# Mode_Switch.net
KiCad netlist of a schematic drawn in Altium Designer
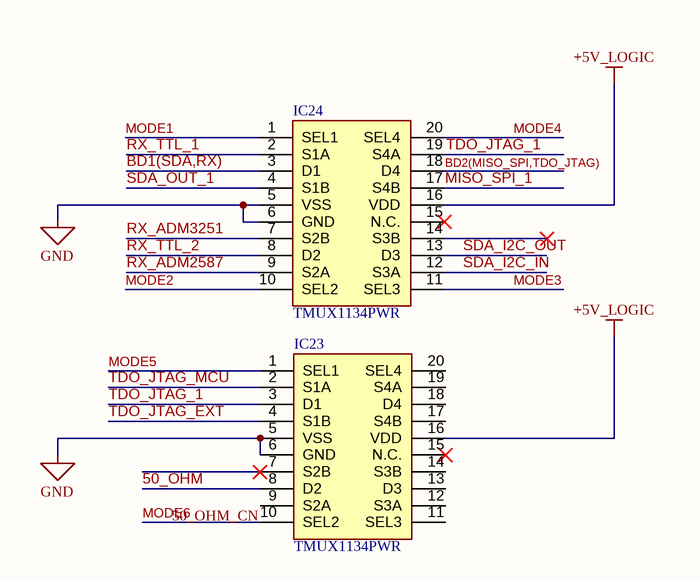
[diagram p0: Mode Switch.SchDoc]

(export (version "E")
  (design (tool "Eeschema 10.0.6"))
  (components
    (comp (ref "IC23")
      (value "TMUX1134PWR")
      (footprint "SamacSys:SOP65P640X120-20N")
      (description "Integrated Circuit")
      (fields (field (name "MOUSER PART NUMBER") "595-TMUX1134PWR"))
      (libsource (lib "*") (part "TMUX1134PWR"))
    )
    (comp (ref "IC24")
      (value "TMUX1134PWR")
      (footprint "SamacSys:SOP65P640X120-20N")
      (description "Integrated Circuit")
      (fields (field (name "MOUSER PART NUMBER") "595-TMUX1134PWR"))
      (libsource (lib "*") (part "TMUX1134PWR"))
    )
  )
  (nets
    (net (code "1") (name "+5V_LOGIC") (class "Default")
      (node (ref "IC23") (pin "16") (pinfunction "VDD_16") (pintype "passive"))
      (node (ref "IC24") (pin "16") (pinfunction "VDD_16") (pintype "passive"))
    )
    (net (code "2") (name "/50_OHM") (class "Default")
      (node (ref "IC23") (pin "8") (pinfunction "D2_8") (pintype "passive"))
    )
    (net (code "3") (name "/50_OHM_CN") (class "Default")
      (node (ref "IC23") (pin "9") (pinfunction "S2A_9") (pintype "passive"))
    )
    (net (code "4") (name "/BD1(SDA,RX)") (class "Default")
      (node (ref "IC24") (pin "3") (pinfunction "D1_3") (pintype "passive"))
    )
    (net (code "5") (name "/BD2(MISO_SPI,TDO_JTAG)") (class "Default")
      (node (ref "IC24") (pin "18") (pinfunction "D4_18") (pintype "passive"))
    )
    (net (code "6") (name "/MISO_SPI_1") (class "Default")
      (node (ref "IC24") (pin "17") (pinfunction "S4B_17") (pintype "passive"))
    )
    (net (code "7") (name "/MODE1") (class "Default")
      (node (ref "IC24") (pin "1") (pinfunction "SEL1_1") (pintype "passive"))
    )
    (net (code "8") (name "/MODE2") (class "Default")
      (node (ref "IC24") (pin "10") (pinfunction "SEL2_10") (pintype "passive"))
    )
    (net (code "9") (name "/MODE3") (class "Default")
      (node (ref "IC24") (pin "11") (pinfunction "SEL3_11") (pintype "passive"))
    )
    (net (code "10") (name "/MODE4") (class "Default")
      (node (ref "IC24") (pin "20") (pinfunction "SEL4_20") (pintype "passive"))
    )
    (net (code "11") (name "/MODE5") (class "Default")
      (node (ref "IC23") (pin "1") (pinfunction "SEL1_1") (pintype "passive"))
    )
    (net (code "12") (name "/MODE6") (class "Default")
      (node (ref "IC23") (pin "10") (pinfunction "SEL2_10") (pintype "passive"))
    )
    (net (code "13") (name "/RX_ADM2587") (class "Default")
      (node (ref "IC24") (pin "9") (pinfunction "S2A_9") (pintype "passive"))
    )
    (net (code "14") (name "/RX_ADM3251") (class "Default")
      (node (ref "IC24") (pin "7") (pinfunction "S2B_7") (pintype "passive"))
    )
    (net (code "15") (name "/RX_TTL_1") (class "Default")
      (node (ref "IC24") (pin "2") (pinfunction "S1A_2") (pintype "passive"))
    )
    (net (code "16") (name "/RX_TTL_2") (class "Default")
      (node (ref "IC24") (pin "8") (pinfunction "D2_8") (pintype "passive"))
    )
    (net (code "17") (name "/SDA_I2C_IN") (class "Default")
      (node (ref "IC24") (pin "12") (pinfunction "S3A_12") (pintype "passive"))
    )
    (net (code "18") (name "/SDA_I2C_OUT") (class "Default")
      (node (ref "IC24") (pin "13") (pinfunction "D3_13") (pintype "passive"))
    )
    (net (code "19") (name "/SDA_OUT_1") (class "Default")
      (node (ref "IC24") (pin "4") (pinfunction "S1B_4") (pintype "passive"))
    )
    (net (code "20") (name "/TDO_JTAG_1") (class "Default")
      (node (ref "IC23") (pin "3") (pinfunction "D1_3") (pintype "passive"))
      (node (ref "IC24") (pin "19") (pinfunction "S4A_19") (pintype "passive"))
    )
    (net (code "21") (name "/TDO_JTAG_EXT") (class "Default")
      (node (ref "IC23") (pin "4") (pinfunction "S1B_4") (pintype "passive"))
    )
    (net (code "22") (name "/TDO_JTAG_MCU") (class "Default")
      (node (ref "IC23") (pin "2") (pinfunction "S1A_2") (pintype "passive"))
    )
    (net (code "23") (name "GND") (class "Default")
      (node (ref "IC23") (pin "5") (pinfunction "VSS_5") (pintype "passive"))
      (node (ref "IC23") (pin "6") (pinfunction "GND_6") (pintype "passive"))
      (node (ref "IC24") (pin "5") (pinfunction "VSS_5") (pintype "passive"))
      (node (ref "IC24") (pin "6") (pinfunction "GND_6") (pintype "passive"))
    )
    (net (code "24") (name "unconnected-(IC23-D3-Pad13)") (class "Default")
      (node (ref "IC23") (pin "13") (pinfunction "D3_13") (pintype "passive"))
    )
    (net (code "25") (name "unconnected-(IC23-D4-Pad18)") (class "Default")
      (node (ref "IC23") (pin "18") (pinfunction "D4_18") (pintype "passive"))
    )
    (net (code "26") (name "unconnected-(IC23-N.C.-Pad15)") (class "Default")
      (node (ref "IC23") (pin "15") (pinfunction "N.C._15") (pintype "passive+no_connect"))
    )
    (net (code "27") (name "unconnected-(IC23-S2B-Pad7)") (class "Default")
      (node (ref "IC23") (pin "7") (pinfunction "S2B_7") (pintype "passive+no_connect"))
    )
    (net (code "28") (name "unconnected-(IC23-S3A-Pad12)") (class "Default")
      (node (ref "IC23") (pin "12") (pinfunction "S3A_12") (pintype "passive"))
    )
    (net (code "29") (name "unconnected-(IC23-S3B-Pad14)") (class "Default")
      (node (ref "IC23") (pin "14") (pinfunction "S3B_14") (pintype "passive"))
    )
    (net (code "30") (name "unconnected-(IC23-S4A-Pad19)") (class "Default")
      (node (ref "IC23") (pin "19") (pinfunction "S4A_19") (pintype "passive"))
    )
    (net (code "31") (name "unconnected-(IC23-S4B-Pad17)") (class "Default")
      (node (ref "IC23") (pin "17") (pinfunction "S4B_17") (pintype "passive"))
    )
    (net (code "32") (name "unconnected-(IC23-SEL3-Pad11)") (class "Default")
      (node (ref "IC23") (pin "11") (pinfunction "SEL3_11") (pintype "passive"))
    )
    (net (code "33") (name "unconnected-(IC23-SEL4-Pad20)") (class "Default")
      (node (ref "IC23") (pin "20") (pinfunction "SEL4_20") (pintype "passive"))
    )
    (net (code "34") (name "unconnected-(IC24-N.C.-Pad15)") (class "Default")
      (node (ref "IC24") (pin "15") (pinfunction "N.C._15") (pintype "passive+no_connect"))
    )
    (net (code "35") (name "unconnected-(IC24-S3B-Pad14)") (class "Default")
      (node (ref "IC24") (pin "14") (pinfunction "S3B_14") (pintype "passive+no_connect"))
    )
  )
)
